# Board.net
KiCad netlist of a schematic drawn in EAGLE
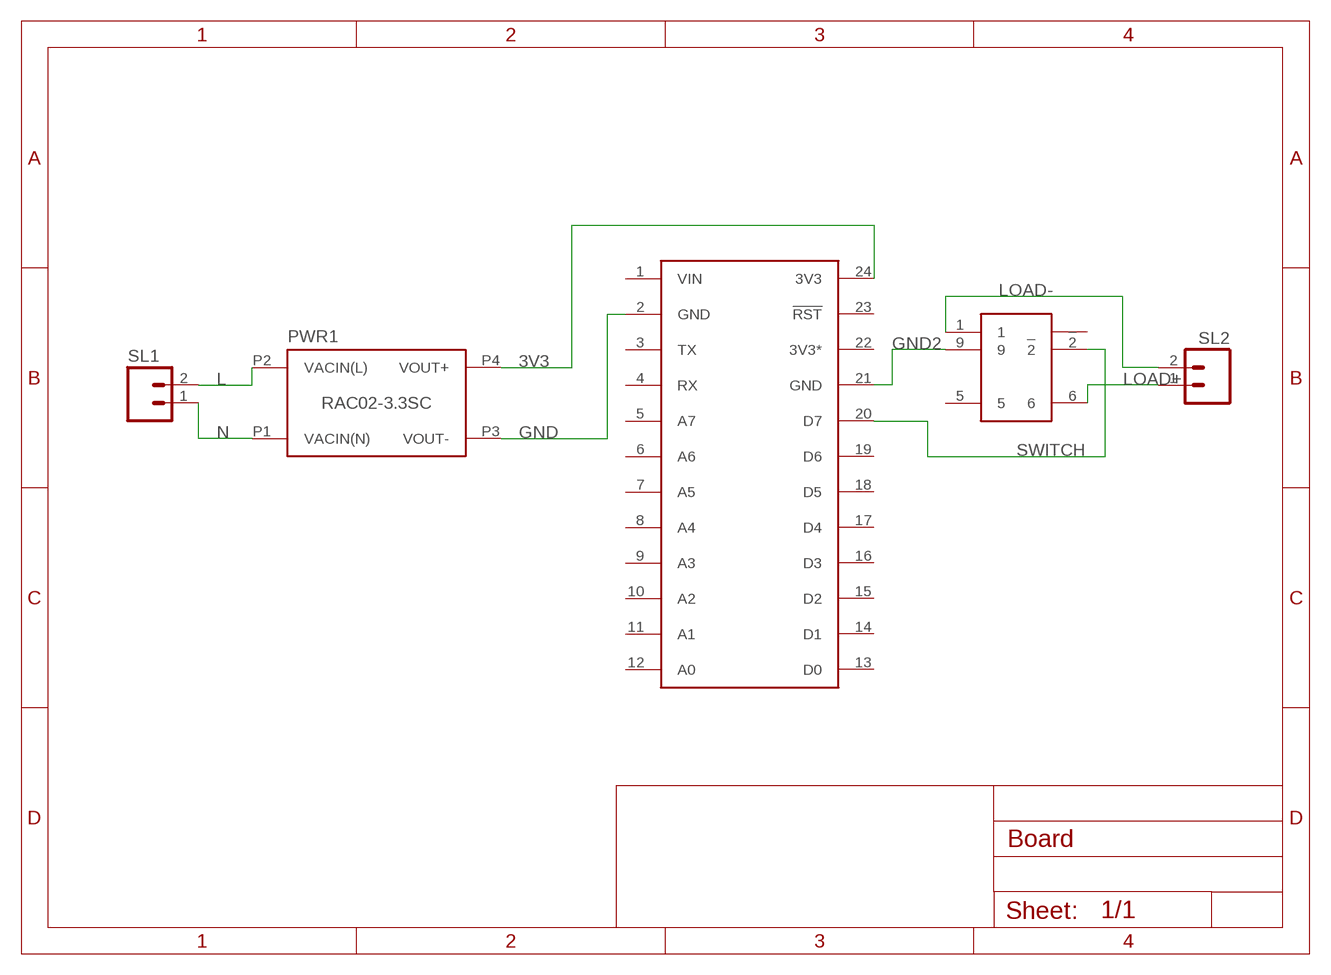
[diagram p0: schematic, sheet 1]

(export (version "E")
  (design (tool "Eeschema 10.0.6"))
  (components
    (comp (ref "CORE")
      (value "SPARK_CORECORE")
      (footprint "eagle-import:SPARK_CORE")
      (libsource (lib "eagle-import") (part "SPARK_CORECORE"))
    )
    (comp (ref "PWR1")
      (value "RAC02-3.3SC")
      (footprint "eagle-import:LOW_PROFILE_POWER_MODULE")
      (libsource (lib "eagle-import") (part "RACSC02-3.3"))
    )
    (comp (ref "RELAY1")
      (value "AZ9571AZ9571")
      (footprint "eagle-import:AZ9571")
      (libsource (lib "eagle-import") (part "AZ9571AZ9571"))
    )
    (comp (ref "SL1")
      (value "M02")
      (footprint "eagle-import:02P")
      (libsource (lib "eagle-import") (part "M02"))
    )
    (comp (ref "SL2")
      (value "M02")
      (footprint "eagle-import:02P")
      (libsource (lib "eagle-import") (part "M02"))
    )
  )
  (nets
    (net (code "1") (name "/3V3") (class "Default")
      (node (ref "CORE") (pin "24") (pinfunction "3V3_24") (pintype "power_in"))
      (node (ref "PWR1") (pin "P4") (pinfunction "VOUT+_P4") (pintype "power_in"))
    )
    (net (code "2") (name "/3V3*") (class "Default")
      (node (ref "CORE") (pin "22") (pinfunction "3V3*_22") (pintype "power_in"))
    )
    (net (code "3") (name "/GND") (class "Default")
      (node (ref "CORE") (pin "2") (pinfunction "GND_2") (pintype "power_in"))
      (node (ref "PWR1") (pin "P3") (pinfunction "VOUT-_P3") (pintype "power_in"))
    )
    (net (code "4") (name "/GND2") (class "Default")
      (node (ref "CORE") (pin "21") (pinfunction "GND_21") (pintype "power_in"))
      (node (ref "RELAY1") (pin "9") (pinfunction "9_9") (pintype "bidirectional"))
    )
    (net (code "5") (name "/L") (class "Default")
      (node (ref "PWR1") (pin "P2") (pinfunction "VACIN(L)_P2") (pintype "power_in"))
      (node (ref "SL1") (pin "2") (pinfunction "2_2") (pintype "passive"))
    )
    (net (code "6") (name "/LOAD+") (class "Default")
      (node (ref "RELAY1") (pin "6") (pinfunction "6_6") (pintype "bidirectional"))
      (node (ref "SL2") (pin "1") (pinfunction "1_1") (pintype "passive"))
    )
    (net (code "7") (name "/LOAD-") (class "Default")
      (node (ref "RELAY1") (pin "1") (pinfunction "1_1") (pintype "bidirectional"))
      (node (ref "SL2") (pin "2") (pinfunction "2_2") (pintype "passive"))
    )
    (net (code "8") (name "/N") (class "Default")
      (node (ref "PWR1") (pin "P1") (pinfunction "VACIN(N)_P1") (pintype "power_in"))
      (node (ref "SL1") (pin "1") (pinfunction "1_1") (pintype "passive"))
    )
    (net (code "9") (name "/SWITCH") (class "Default")
      (node (ref "CORE") (pin "20") (pinfunction "D7_20") (pintype "bidirectional"))
      (node (ref "RELAY1") (pin "2") (pinfunction "2_2") (pintype "bidirectional"))
    )
    (net (code "10") (name "/VIN") (class "Default")
      (node (ref "CORE") (pin "1") (pinfunction "VIN_1") (pintype "power_in"))
    )
    (net (code "11") (name "unconnected-(CORE-A0-Pad12)") (class "Default")
      (node (ref "CORE") (pin "12") (pinfunction "A0_12") (pintype "bidirectional"))
    )
    (net (code "12") (name "unconnected-(CORE-A1-Pad11)") (class "Default")
      (node (ref "CORE") (pin "11") (pinfunction "A1_11") (pintype "bidirectional"))
    )
    (net (code "13") (name "unconnected-(CORE-A2-Pad10)") (class "Default")
      (node (ref "CORE") (pin "10") (pinfunction "A2_10") (pintype "bidirectional"))
    )
    (net (code "14") (name "unconnected-(CORE-A3-Pad9)") (class "Default")
      (node (ref "CORE") (pin "9") (pinfunction "A3_9") (pintype "bidirectional"))
    )
    (net (code "15") (name "unconnected-(CORE-A4-Pad8)") (class "Default")
      (node (ref "CORE") (pin "8") (pinfunction "A4_8") (pintype "bidirectional"))
    )
    (net (code "16") (name "unconnected-(CORE-A5-Pad7)") (class "Default")
      (node (ref "CORE") (pin "7") (pinfunction "A5_7") (pintype "bidirectional"))
    )
    (net (code "17") (name "unconnected-(CORE-A6-Pad6)") (class "Default")
      (node (ref "CORE") (pin "6") (pinfunction "A6_6") (pintype "bidirectional"))
    )
    (net (code "18") (name "unconnected-(CORE-A7-Pad5)") (class "Default")
      (node (ref "CORE") (pin "5") (pinfunction "A7_5") (pintype "bidirectional"))
    )
    (net (code "19") (name "unconnected-(CORE-D0-Pad13)") (class "Default")
      (node (ref "CORE") (pin "13") (pinfunction "D0_13") (pintype "bidirectional"))
    )
    (net (code "20") (name "unconnected-(CORE-D1-Pad14)") (class "Default")
      (node (ref "CORE") (pin "14") (pinfunction "D1_14") (pintype "bidirectional"))
    )
    (net (code "21") (name "unconnected-(CORE-D2-Pad15)") (class "Default")
      (node (ref "CORE") (pin "15") (pinfunction "D2_15") (pintype "bidirectional"))
    )
    (net (code "22") (name "unconnected-(CORE-D3-Pad16)") (class "Default")
      (node (ref "CORE") (pin "16") (pinfunction "D3_16") (pintype "bidirectional"))
    )
    (net (code "23") (name "unconnected-(CORE-D4-Pad17)") (class "Default")
      (node (ref "CORE") (pin "17") (pinfunction "D4_17") (pintype "bidirectional"))
    )
    (net (code "24") (name "unconnected-(CORE-D5-Pad18)") (class "Default")
      (node (ref "CORE") (pin "18") (pinfunction "D5_18") (pintype "bidirectional"))
    )
    (net (code "25") (name "unconnected-(CORE-D6-Pad19)") (class "Default")
      (node (ref "CORE") (pin "19") (pinfunction "D6_19") (pintype "bidirectional"))
    )
    (net (code "26") (name "unconnected-(CORE-RX-Pad4)") (class "Default")
      (node (ref "CORE") (pin "4") (pinfunction "RX_4") (pintype "bidirectional"))
    )
    (net (code "27") (name "unconnected-(CORE-TX-Pad3)") (class "Default")
      (node (ref "CORE") (pin "3") (pinfunction "TX_3") (pintype "bidirectional"))
    )
    (net (code "28") (name "unconnected-(CORE-~{RST}-Pad23)") (class "Default")
      (node (ref "CORE") (pin "23") (pinfunction "~{RST}_23") (pintype "bidirectional"))
    )
    (net (code "29") (name "unconnected-(RELAY1-Pad5)") (class "Default")
      (node (ref "RELAY1") (pin "5") (pinfunction "5_5") (pintype "bidirectional"))
    )
    (net (code "30") (name "unconnected-(RELAY1-Pad_)") (class "Default")
      (node (ref "RELAY1") (pin "_") (pinfunction "___") (pintype "bidirectional"))
    )
  )
)
